# KillSwitch_MotorOut.net
KiCad netlist of a schematic drawn in Altium Designer
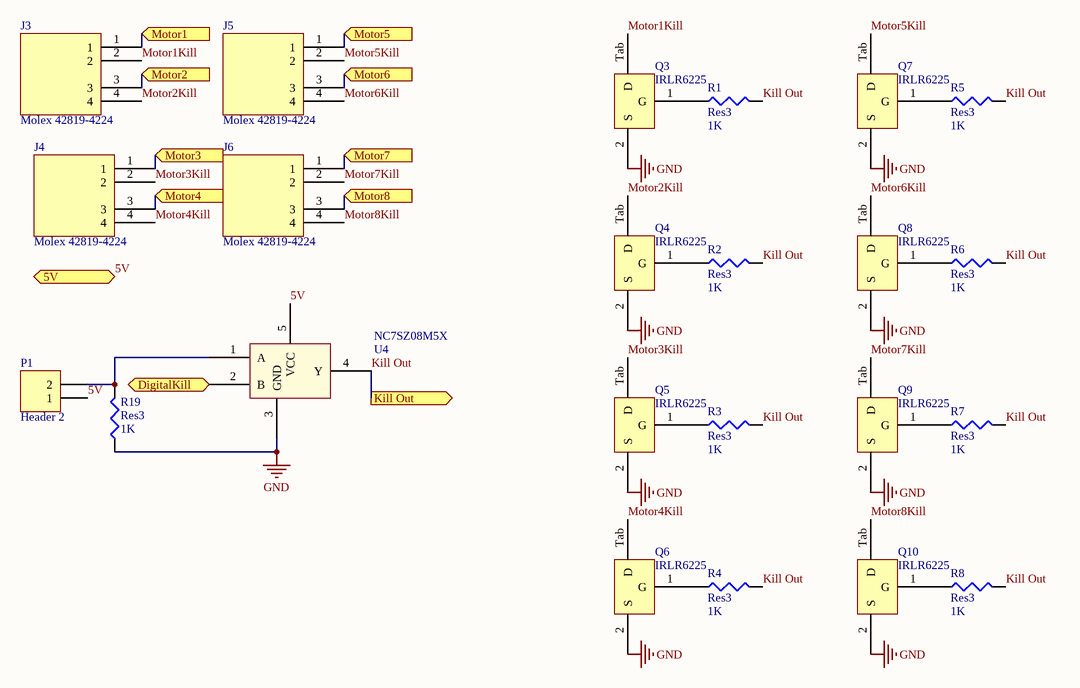
[diagram p0: KillSwitch_MotorOut.SchDoc]

(export (version "E")
  (design (tool "Eeschema 10.0.6"))
  (components
    (comp (ref "J3")
      (value "Molex 42819-4224")
      (footprint "MOLEX_42819-4224")
      (libsource (lib "Molex_42819-4224") (part "Molex_42819-4224"))
    )
    (comp (ref "J4")
      (value "Molex 42819-4224")
      (footprint "MOLEX_42819-4224")
      (libsource (lib "Molex_42819-4224") (part "Molex_42819-4224"))
    )
    (comp (ref "J5")
      (value "Molex 42819-4224")
      (footprint "MOLEX_42819-4224")
      (libsource (lib "Molex_42819-4224") (part "Molex_42819-4224"))
    )
    (comp (ref "J6")
      (value "Molex 42819-4224")
      (footprint "MOLEX_42819-4224")
      (libsource (lib "Molex_42819-4224") (part "Molex_42819-4224"))
    )
    (comp (ref "NC7SZ08M5X")
      (value "U4")
      (footprint "NC7SZ08M5X")
      (libsource (lib "NC7SZ08M5X") (part "NC7SZ08M5X"))
    )
    (comp (ref "P1")
      (value "Header 2")
      (footprint "HDR1X2")
      (description "Header, 2-Pin")
      (fields (field (name "PUBLISHER") "Altium Limited"))
      (libsource (lib "Miscellaneous Connectors") (part "Header 2"))
    )
    (comp (ref "Q3") (value "IRLR6225") (footprint "IRLR6225") (libsource (lib "IRLR6225") (part "IRLR6225")))
    (comp (ref "Q4") (value "IRLR6225") (footprint "IRLR6225") (libsource (lib "IRLR6225") (part "IRLR6225")))
    (comp (ref "Q5") (value "IRLR6225") (footprint "IRLR6225") (libsource (lib "IRLR6225") (part "IRLR6225")))
    (comp (ref "Q6") (value "IRLR6225") (footprint "IRLR6225") (libsource (lib "IRLR6225") (part "IRLR6225")))
    (comp (ref "Q7") (value "IRLR6225") (footprint "IRLR6225") (libsource (lib "IRLR6225") (part "IRLR6225")))
    (comp (ref "Q8") (value "IRLR6225") (footprint "IRLR6225") (libsource (lib "IRLR6225") (part "IRLR6225")))
    (comp (ref "Q9") (value "IRLR6225") (footprint "IRLR6225") (libsource (lib "IRLR6225") (part "IRLR6225")))
    (comp (ref "Q10")
      (value "IRLR6225")
      (footprint "IRLR6225")
      (libsource (lib "IRLR6225") (part "IRLR6225"))
    )
    (comp (ref "R1")
      (value "Res3")
      (footprint "J1-0603")
      (description "Resistor")
      (fields (field (name "ALTIUM_VALUE") "1K") (field (name "PUBLISHER") "Altium Limited"))
      (libsource (lib "Miscellaneous Devices") (part "Res3"))
    )
    (comp (ref "R2")
      (value "Res3")
      (footprint "J1-0603")
      (description "Resistor")
      (fields (field (name "ALTIUM_VALUE") "1K") (field (name "PUBLISHER") "Altium Limited"))
      (libsource (lib "Miscellaneous Devices") (part "Res3"))
    )
    (comp (ref "R3")
      (value "Res3")
      (footprint "J1-0603")
      (description "Resistor")
      (fields (field (name "ALTIUM_VALUE") "1K") (field (name "PUBLISHER") "Altium Limited"))
      (libsource (lib "Miscellaneous Devices") (part "Res3"))
    )
    (comp (ref "R4")
      (value "Res3")
      (footprint "J1-0603")
      (description "Resistor")
      (fields (field (name "ALTIUM_VALUE") "1K") (field (name "PUBLISHER") "Altium Limited"))
      (libsource (lib "Miscellaneous Devices") (part "Res3"))
    )
    (comp (ref "R5")
      (value "Res3")
      (footprint "J1-0603")
      (description "Resistor")
      (fields (field (name "ALTIUM_VALUE") "1K") (field (name "PUBLISHER") "Altium Limited"))
      (libsource (lib "Miscellaneous Devices") (part "Res3"))
    )
    (comp (ref "R6")
      (value "Res3")
      (footprint "J1-0603")
      (description "Resistor")
      (fields (field (name "ALTIUM_VALUE") "1K") (field (name "PUBLISHER") "Altium Limited"))
      (libsource (lib "Miscellaneous Devices") (part "Res3"))
    )
    (comp (ref "R7")
      (value "Res3")
      (footprint "J1-0603")
      (description "Resistor")
      (fields (field (name "ALTIUM_VALUE") "1K") (field (name "PUBLISHER") "Altium Limited"))
      (libsource (lib "Miscellaneous Devices") (part "Res3"))
    )
    (comp (ref "R8")
      (value "Res3")
      (footprint "J1-0603")
      (description "Resistor")
      (fields (field (name "ALTIUM_VALUE") "1K") (field (name "PUBLISHER") "Altium Limited"))
      (libsource (lib "Miscellaneous Devices") (part "Res3"))
    )
    (comp (ref "R19")
      (value "Res3")
      (footprint "J1-0603")
      (description "Resistor")
      (fields (field (name "ALTIUM_VALUE") "1K") (field (name "PUBLISHER") "Altium Limited"))
      (libsource (lib "Miscellaneous Devices") (part "Res3"))
    )
  )
  (nets
    (net (code "1") (name "/5V") (class "Default")
      (node (ref "NC7SZ08M5X") (pin "5") (pinfunction "VCC_5") (pintype "passive"))
      (node (ref "P1") (pin "1") (pinfunction "1_1") (pintype "passive"))
    )
    (net (code "2") (name "/DigitalKill") (class "Default")
      (node (ref "NC7SZ08M5X") (pin "2") (pinfunction "B_2") (pintype "passive"))
    )
    (net (code "3") (name "/Kill Out") (class "Default")
      (node (ref "NC7SZ08M5X") (pin "4") (pinfunction "Y_4") (pintype "passive"))
      (node (ref "R1") (pin "2") (pinfunction "2_2") (pintype "passive"))
      (node (ref "R2") (pin "2") (pinfunction "2_2") (pintype "passive"))
      (node (ref "R3") (pin "2") (pinfunction "2_2") (pintype "passive"))
      (node (ref "R4") (pin "2") (pinfunction "2_2") (pintype "passive"))
      (node (ref "R5") (pin "2") (pinfunction "2_2") (pintype "passive"))
      (node (ref "R6") (pin "2") (pinfunction "2_2") (pintype "passive"))
      (node (ref "R7") (pin "2") (pinfunction "2_2") (pintype "passive"))
      (node (ref "R8") (pin "2") (pinfunction "2_2") (pintype "passive"))
    )
    (net (code "4") (name "/Motor1") (class "Default")
      (node (ref "J3") (pin "1") (pinfunction "1_1") (pintype "passive"))
    )
    (net (code "5") (name "/Motor1Kill") (class "Default")
      (node (ref "J3") (pin "2") (pinfunction "2_2") (pintype "passive"))
      (node (ref "Q3") (pin "Tab") (pinfunction "D_Tab") (pintype "passive"))
    )
    (net (code "6") (name "/Motor2") (class "Default")
      (node (ref "J3") (pin "3") (pinfunction "3_3") (pintype "passive"))
    )
    (net (code "7") (name "/Motor2Kill") (class "Default")
      (node (ref "J3") (pin "4") (pinfunction "4_4") (pintype "passive"))
      (node (ref "Q4") (pin "Tab") (pinfunction "D_Tab") (pintype "passive"))
    )
    (net (code "8") (name "/Motor3") (class "Default")
      (node (ref "J4") (pin "1") (pinfunction "1_1") (pintype "passive"))
    )
    (net (code "9") (name "/Motor3Kill") (class "Default")
      (node (ref "J4") (pin "2") (pinfunction "2_2") (pintype "passive"))
      (node (ref "Q5") (pin "Tab") (pinfunction "D_Tab") (pintype "passive"))
    )
    (net (code "10") (name "/Motor4") (class "Default")
      (node (ref "J4") (pin "3") (pinfunction "3_3") (pintype "passive"))
    )
    (net (code "11") (name "/Motor4Kill") (class "Default")
      (node (ref "J4") (pin "4") (pinfunction "4_4") (pintype "passive"))
      (node (ref "Q6") (pin "Tab") (pinfunction "D_Tab") (pintype "passive"))
    )
    (net (code "12") (name "/Motor5") (class "Default")
      (node (ref "J5") (pin "1") (pinfunction "1_1") (pintype "passive"))
    )
    (net (code "13") (name "/Motor5Kill") (class "Default")
      (node (ref "J5") (pin "2") (pinfunction "2_2") (pintype "passive"))
      (node (ref "Q7") (pin "Tab") (pinfunction "D_Tab") (pintype "passive"))
    )
    (net (code "14") (name "/Motor6") (class "Default")
      (node (ref "J5") (pin "3") (pinfunction "3_3") (pintype "passive"))
    )
    (net (code "15") (name "/Motor6Kill") (class "Default")
      (node (ref "J5") (pin "4") (pinfunction "4_4") (pintype "passive"))
      (node (ref "Q8") (pin "Tab") (pinfunction "D_Tab") (pintype "passive"))
    )
    (net (code "16") (name "/Motor7") (class "Default")
      (node (ref "J6") (pin "1") (pinfunction "1_1") (pintype "passive"))
    )
    (net (code "17") (name "/Motor7Kill") (class "Default")
      (node (ref "J6") (pin "2") (pinfunction "2_2") (pintype "passive"))
      (node (ref "Q9") (pin "Tab") (pinfunction "D_Tab") (pintype "passive"))
    )
    (net (code "18") (name "/Motor8") (class "Default")
      (node (ref "J6") (pin "3") (pinfunction "3_3") (pintype "passive"))
    )
    (net (code "19") (name "/Motor8Kill") (class "Default")
      (node (ref "J6") (pin "4") (pinfunction "4_4") (pintype "passive"))
      (node (ref "Q10") (pin "Tab") (pinfunction "D_Tab") (pintype "passive"))
    )
    (net (code "20") (name "GND") (class "Default")
      (node (ref "NC7SZ08M5X") (pin "3") (pinfunction "GND_3") (pintype "passive"))
      (node (ref "Q10") (pin "2") (pinfunction "S_2") (pintype "passive"))
      (node (ref "Q3") (pin "2") (pinfunction "S_2") (pintype "passive"))
      (node (ref "Q4") (pin "2") (pinfunction "S_2") (pintype "passive"))
      (node (ref "Q5") (pin "2") (pinfunction "S_2") (pintype "passive"))
      (node (ref "Q6") (pin "2") (pinfunction "S_2") (pintype "passive"))
      (node (ref "Q7") (pin "2") (pinfunction "S_2") (pintype "passive"))
      (node (ref "Q8") (pin "2") (pinfunction "S_2") (pintype "passive"))
      (node (ref "Q9") (pin "2") (pinfunction "S_2") (pintype "passive"))
      (node (ref "R19") (pin "1") (pinfunction "1_1") (pintype "passive"))
    )
    (net (code "21") (name "Net-(NC7SZ08M5X-A)") (class "Default")
      (node (ref "NC7SZ08M5X") (pin "1") (pinfunction "A_1") (pintype "passive"))
      (node (ref "P1") (pin "2") (pinfunction "2_2") (pintype "passive"))
      (node (ref "R19") (pin "2") (pinfunction "2_2") (pintype "passive"))
    )
    (net (code "22") (name "Net-(Q3-G)") (class "Default")
      (node (ref "Q3") (pin "1") (pinfunction "G_1") (pintype "passive"))
      (node (ref "R1") (pin "1") (pinfunction "1_1") (pintype "passive"))
    )
    (net (code "23") (name "Net-(Q4-G)") (class "Default")
      (node (ref "Q4") (pin "1") (pinfunction "G_1") (pintype "passive"))
      (node (ref "R2") (pin "1") (pinfunction "1_1") (pintype "passive"))
    )
    (net (code "24") (name "Net-(Q5-G)") (class "Default")
      (node (ref "Q5") (pin "1") (pinfunction "G_1") (pintype "passive"))
      (node (ref "R3") (pin "1") (pinfunction "1_1") (pintype "passive"))
    )
    (net (code "25") (name "Net-(Q6-G)") (class "Default")
      (node (ref "Q6") (pin "1") (pinfunction "G_1") (pintype "passive"))
      (node (ref "R4") (pin "1") (pinfunction "1_1") (pintype "passive"))
    )
    (net (code "26") (name "Net-(Q7-G)") (class "Default")
      (node (ref "Q7") (pin "1") (pinfunction "G_1") (pintype "passive"))
      (node (ref "R5") (pin "1") (pinfunction "1_1") (pintype "passive"))
    )
    (net (code "27") (name "Net-(Q8-G)") (class "Default")
      (node (ref "Q8") (pin "1") (pinfunction "G_1") (pintype "passive"))
      (node (ref "R6") (pin "1") (pinfunction "1_1") (pintype "passive"))
    )
    (net (code "28") (name "Net-(Q9-G)") (class "Default")
      (node (ref "Q9") (pin "1") (pinfunction "G_1") (pintype "passive"))
      (node (ref "R7") (pin "1") (pinfunction "1_1") (pintype "passive"))
    )
    (net (code "29") (name "Net-(Q10-G)") (class "Default")
      (node (ref "Q10") (pin "1") (pinfunction "G_1") (pintype "passive"))
      (node (ref "R8") (pin "1") (pinfunction "1_1") (pintype "passive"))
    )
  )
)
